# buffers_5bits.net
KiCad netlist of a schematic drawn in Altium Designer
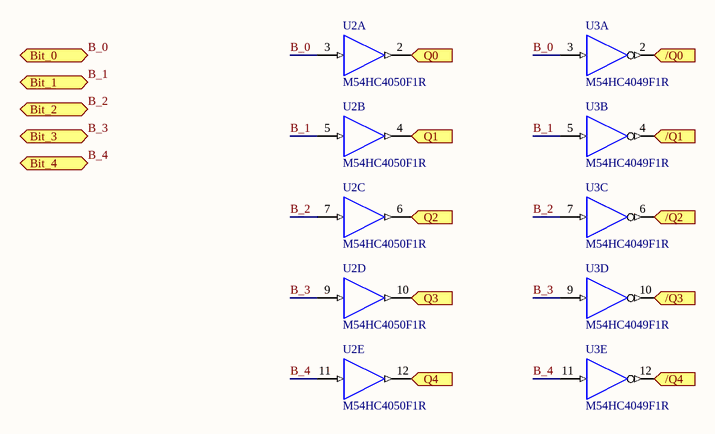
[diagram p0: buffers_5bits.SchDoc]

(export (version "E")
  (design (tool "Eeschema 10.0.6"))
  (components
    (comp (ref "U2")
      (value "M54HC4050F1R")
      (footprint "DIP16")
      (description "Hex Buffer/Converter Non-Inverting")
      (fields (field (name "PUBLISHER") "Altium Limited"))
      (libsource (lib "ST Logic Gate") (part "M54HC4050F1R"))
    )
    (comp (ref "U3")
      (value "M54HC4049F1R")
      (footprint "DIP16")
      (description "Hex Buffer/Converter Invertering")
      (fields (field (name "PUBLISHER") "Altium Limited"))
      (libsource (lib "ST Logic Gate") (part "M54HC4049F1R"))
    )
  )
  (nets
    (net (code "1") (name "/B_0") (class "Default")
      (node (ref "U2") (pin "3") (pinfunction "A_3") (pintype "input"))
      (node (ref "U3") (pin "3") (pinfunction "A_3") (pintype "input"))
    )
    (net (code "2") (name "/B_1") (class "Default")
      (node (ref "U2") (pin "5") (pinfunction "A_5") (pintype "input"))
      (node (ref "U3") (pin "5") (pinfunction "A_5") (pintype "input"))
    )
    (net (code "3") (name "/B_2") (class "Default")
      (node (ref "U2") (pin "7") (pinfunction "A_7") (pintype "input"))
      (node (ref "U3") (pin "7") (pinfunction "A_7") (pintype "input"))
    )
    (net (code "4") (name "/B_3") (class "Default")
      (node (ref "U2") (pin "9") (pinfunction "A_9") (pintype "input"))
      (node (ref "U3") (pin "9") (pinfunction "A_9") (pintype "input"))
    )
    (net (code "5") (name "/B_4") (class "Default")
      (node (ref "U2") (pin "11") (pinfunction "A_11") (pintype "input"))
      (node (ref "U3") (pin "11") (pinfunction "A_11") (pintype "input"))
    )
    (net (code "6") (name "/Q0") (class "Default")
      (node (ref "U2") (pin "2") (pinfunction "Y_2") (pintype "output"))
    )
    (net (code "7") (name "/Q1") (class "Default")
      (node (ref "U2") (pin "4") (pinfunction "Y_4") (pintype "output"))
    )
    (net (code "8") (name "/Q2") (class "Default")
      (node (ref "U2") (pin "6") (pinfunction "Y_6") (pintype "output"))
    )
    (net (code "9") (name "/Q3") (class "Default")
      (node (ref "U2") (pin "10") (pinfunction "Y_10") (pintype "output"))
    )
    (net (code "10") (name "/Q4") (class "Default")
      (node (ref "U2") (pin "12") (pinfunction "Y_12") (pintype "output"))
    )
    (net (code "11") (name "/{slash}Q0") (class "Default")
      (node (ref "U3") (pin "2") (pinfunction "Y_2") (pintype "output"))
    )
    (net (code "12") (name "/{slash}Q1") (class "Default")
      (node (ref "U3") (pin "4") (pinfunction "Y_4") (pintype "output"))
    )
    (net (code "13") (name "/{slash}Q2") (class "Default")
      (node (ref "U3") (pin "6") (pinfunction "Y_6") (pintype "output"))
    )
    (net (code "14") (name "/{slash}Q3") (class "Default")
      (node (ref "U3") (pin "10") (pinfunction "Y_10") (pintype "output"))
    )
    (net (code "15") (name "/{slash}Q4") (class "Default")
      (node (ref "U3") (pin "12") (pinfunction "Y_12") (pintype "output"))
    )
    (net (code "16") (name "GND") (class "Default")
      (node (ref "U2") (pin "8") (pinfunction "GND_8") (pintype "power_in"))
      (node (ref "U3") (pin "8") (pinfunction "GND_8") (pintype "power_in"))
    )
    (net (code "17") (name "VCC") (class "Default")
      (node (ref "U2") (pin "1") (pinfunction "VCC_1") (pintype "power_in"))
      (node (ref "U3") (pin "1") (pinfunction "VCC_1") (pintype "power_in"))
    )
  )
)
